# piezo-preamp-tickler_V0-5.net
KiCad netlist of a schematic drawn in EAGLE
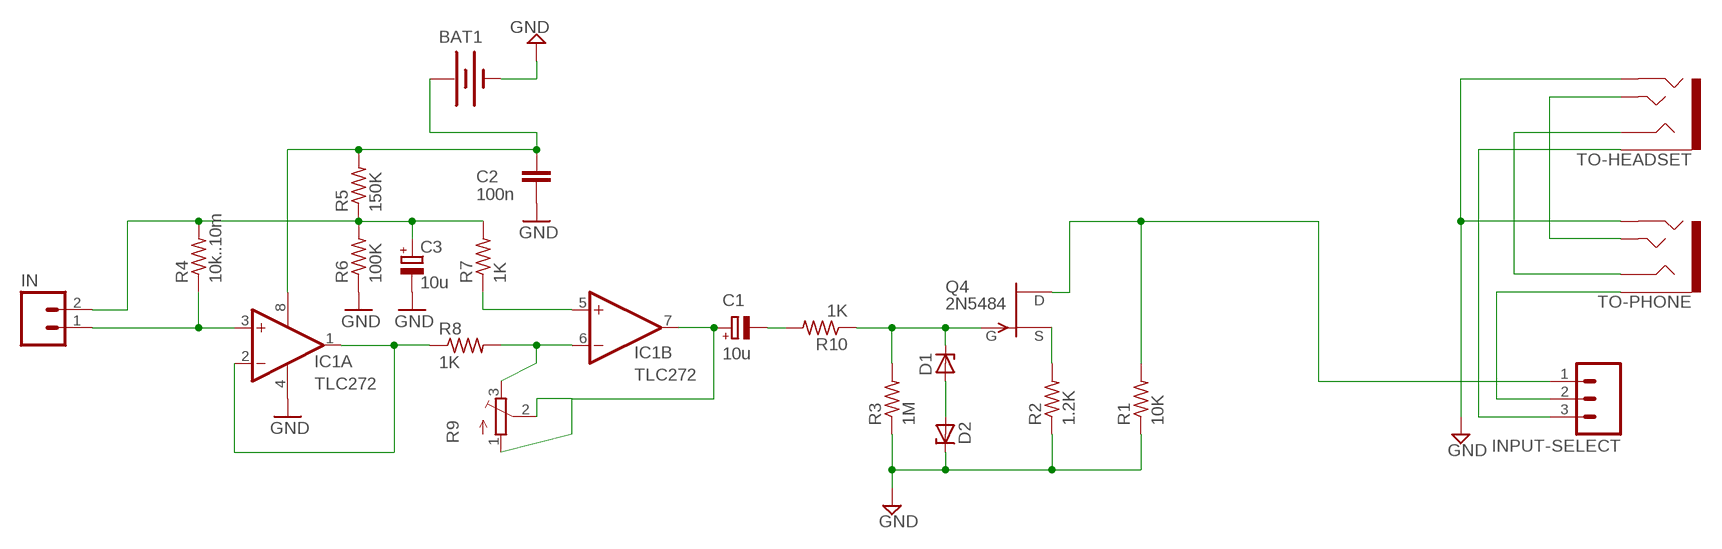
[diagram p0: schematic, sheet 1]

(export (version "E")
  (design (tool "Eeschema 10.0.6"))
  (components
    (comp (ref "BAT1")
      (value "BATTERYA23")
      (footprint "eagle-import:BATTERY-A23")
      (libsource (lib "eagle-import") (part "BATTERYA23"))
    )
    (comp (ref "C1")
      (value "10u")
      (footprint "eagle-import:E2,5-5")
      (libsource (lib "eagle-import") (part "CPOL-EUE2.5-5"))
    )
    (comp (ref "C2")
      (value "100n")
      (footprint "eagle-import:C025-025X050")
      (libsource (lib "eagle-import") (part "C-EU025-025X050"))
    )
    (comp (ref "C3")
      (value "10u")
      (footprint "eagle-import:E2,5-5")
      (libsource (lib "eagle-import") (part "CPOL-EUE2.5-5"))
    )
    (comp (ref "D1")
      (value "1N821")
      (footprint "eagle-import:DO35Z10")
      (libsource (lib "eagle-import") (part "1N821"))
    )
    (comp (ref "D2")
      (value "1N821")
      (footprint "eagle-import:DO35Z10")
      (libsource (lib "eagle-import") (part "1N821"))
    )
    (comp (ref "IC1")
      (value "TLC272")
      (footprint "eagle-import:DIL08")
      (libsource (lib "eagle-import") (part "TLC272P"))
    )
    (comp (ref "IN")
      (value "M02LOCK")
      (footprint "eagle-import:1X02_LOCK")
      (libsource (lib "eagle-import") (part "M02LOCK"))
    )
    (comp (ref "INPUT-SELECT")
      (value "M03LOCK")
      (footprint "eagle-import:1X03_LOCK")
      (libsource (lib "eagle-import") (part "M03LOCK"))
    )
    (comp (ref "Q4")
      (value "2N5484")
      (footprint "eagle-import:TO92-")
      (libsource (lib "eagle-import") (part "?5482N4"))
    )
    (comp (ref "R1")
      (value "10K")
      (footprint "eagle-import:0204V")
      (libsource (lib "eagle-import") (part "R-US_0204/2V"))
    )
    (comp (ref "R2")
      (value "1.2K")
      (footprint "eagle-import:0204V")
      (libsource (lib "eagle-import") (part "R-US_0204/2V"))
    )
    (comp (ref "R3")
      (value "1M")
      (footprint "eagle-import:0204V")
      (libsource (lib "eagle-import") (part "R-US_0204/2V"))
    )
    (comp (ref "R4")
      (value "10k..10m")
      (footprint "eagle-import:0204V")
      (libsource (lib "eagle-import") (part "R-US_0204/2V"))
    )
    (comp (ref "R5")
      (value "150K")
      (footprint "eagle-import:0204V")
      (libsource (lib "eagle-import") (part "R-US_0204/2V"))
    )
    (comp (ref "R6")
      (value "100K")
      (footprint "eagle-import:0204V")
      (libsource (lib "eagle-import") (part "R-US_0204/2V"))
    )
    (comp (ref "R7")
      (value "1K")
      (footprint "eagle-import:0204V")
      (libsource (lib "eagle-import") (part "R-US_0204/2V"))
    )
    (comp (ref "R8")
      (value "1K")
      (footprint "eagle-import:0204V")
      (libsource (lib "eagle-import") (part "R-US_0204/2V"))
    )
    (comp (ref "R9")
      (value "TRIMPOT3386")
      (footprint "eagle-import:TRIM-3386")
      (libsource (lib "eagle-import") (part "TRIMPOT3386"))
    )
    (comp (ref "R10")
      (value "1K")
      (footprint "eagle-import:0204V")
      (libsource (lib "eagle-import") (part "R-US_0204/2V"))
    )
    (comp (ref "TO-HEADSET")
      (value "AUDIO-JACK3")
      (footprint "eagle-import:AUDIO-JACK-TRRS-SMD")
      (libsource (lib "eagle-import") (part "AUDIO-JACK3"))
    )
    (comp (ref "TO-PHONE")
      (value "AUDIO-JACK3")
      (footprint "eagle-import:AUDIO-JACK-TRRS-SMD")
      (libsource (lib "eagle-import") (part "AUDIO-JACK3"))
    )
  )
  (nets
    (net (code "1") (name "GND") (class "Default")
      (node (ref "BAT1") (pin "GND@1") (pinfunction "-_GND@1") (pintype "power_in"))
      (node (ref "C2") (pin "1") (pinfunction "1_1") (pintype "passive"))
      (node (ref "C3") (pin "-") (pinfunction "-_-") (pintype "passive"))
      (node (ref "D2") (pin "C") (pinfunction "C_C") (pintype "passive"))
      (node (ref "IC1") (pin "4") (pinfunction "V-_4") (pintype "power_in"))
      (node (ref "R1") (pin "1") (pinfunction "1_1") (pintype "passive"))
      (node (ref "R2") (pin "1") (pinfunction "1_1") (pintype "passive"))
      (node (ref "R3") (pin "1") (pinfunction "1_1") (pintype "passive"))
      (node (ref "R6") (pin "1") (pinfunction "1_1") (pintype "passive"))
      (node (ref "TO-HEADSET") (pin "RING2") (pinfunction "RING2_RING2") (pintype "bidirectional"))
      (node (ref "TO-PHONE") (pin "RING2") (pinfunction "RING2_RING2") (pintype "bidirectional"))
    )
    (net (code "2") (name "Net-(BAT1-+)") (class "Default")
      (node (ref "BAT1") (pin "PWR@1") (pinfunction "+_PWR@1") (pintype "power_in"))
      (node (ref "C2") (pin "2") (pinfunction "2_2") (pintype "passive"))
      (node (ref "IC1") (pin "8") (pinfunction "V+_8") (pintype "power_in"))
      (node (ref "R5") (pin "2") (pinfunction "2_2") (pintype "passive"))
    )
    (net (code "3") (name "Net-(C1-Pad-)") (class "Default")
      (node (ref "C1") (pin "-") (pinfunction "-_-") (pintype "passive"))
      (node (ref "R10") (pin "2") (pinfunction "2_2") (pintype "passive"))
    )
    (net (code "4") (name "Net-(C3-Pad+)") (class "Default")
      (node (ref "C3") (pin "+") (pinfunction "+_+") (pintype "passive"))
      (node (ref "IN") (pin "2") (pinfunction "2_2") (pintype "passive"))
      (node (ref "R4") (pin "2") (pinfunction "2_2") (pintype "passive"))
      (node (ref "R5") (pin "1") (pinfunction "1_1") (pintype "passive"))
      (node (ref "R6") (pin "2") (pinfunction "2_2") (pintype "passive"))
      (node (ref "R7") (pin "2") (pinfunction "2_2") (pintype "passive"))
    )
    (net (code "5") (name "Net-(D1-PadA)") (class "Default")
      (node (ref "D1") (pin "A") (pinfunction "A_A") (pintype "passive"))
      (node (ref "D2") (pin "A") (pinfunction "A_A") (pintype "passive"))
    )
    (net (code "6") (name "Net-(IC1A-+IN)") (class "Default")
      (node (ref "IC1") (pin "3") (pinfunction "+IN_3") (pintype "input"))
      (node (ref "IN") (pin "1") (pinfunction "1_1") (pintype "passive"))
      (node (ref "R4") (pin "1") (pinfunction "1_1") (pintype "passive"))
    )
    (net (code "7") (name "Net-(IC1A--IN)") (class "Default")
      (node (ref "IC1") (pin "1") (pinfunction "OUT_1") (pintype "output"))
      (node (ref "IC1") (pin "2") (pinfunction "-IN_2") (pintype "input"))
      (node (ref "R8") (pin "1") (pinfunction "1_1") (pintype "passive"))
    )
    (net (code "8") (name "Net-(IC1B-+IN)") (class "Default")
      (node (ref "IC1") (pin "5") (pinfunction "+IN_5") (pintype "input"))
      (node (ref "R7") (pin "1") (pinfunction "1_1") (pintype "passive"))
    )
    (net (code "9") (name "Net-(IC1B--IN)") (class "Default")
      (node (ref "IC1") (pin "6") (pinfunction "-IN_6") (pintype "input"))
      (node (ref "R8") (pin "2") (pinfunction "2_2") (pintype "passive"))
      (node (ref "R9") (pin "3") (pinfunction "E_3") (pintype "passive"))
    )
    (net (code "10") (name "Net-(IC1B-OUT)") (class "Default")
      (node (ref "C1") (pin "+") (pinfunction "+_+") (pintype "passive"))
      (node (ref "IC1") (pin "7") (pinfunction "OUT_7") (pintype "output"))
      (node (ref "R9") (pin "1") (pinfunction "A_1") (pintype "passive"))
      (node (ref "R9") (pin "2") (pinfunction "S_2") (pintype "passive"))
    )
    (net (code "11") (name "Net-(INPUT-SELECT-Pad2)") (class "Default")
      (node (ref "INPUT-SELECT") (pin "2") (pinfunction "2_2") (pintype "passive"))
      (node (ref "TO-PHONE") (pin "EARTH") (pinfunction "EARTH_EARTH") (pintype "bidirectional"))
    )
    (net (code "12") (name "Net-(INPUT-SELECT-Pad3)") (class "Default")
      (node (ref "INPUT-SELECT") (pin "3") (pinfunction "3_3") (pintype "passive"))
      (node (ref "TO-HEADSET") (pin "EARTH") (pinfunction "EARTH_EARTH") (pintype "bidirectional"))
    )
    (net (code "13") (name "Net-(Q4-D)") (class "Default")
      (node (ref "INPUT-SELECT") (pin "1") (pinfunction "1_1") (pintype "passive"))
      (node (ref "Q4") (pin "3") (pinfunction "D_3") (pintype "passive"))
      (node (ref "R1") (pin "2") (pinfunction "2_2") (pintype "passive"))
    )
    (net (code "14") (name "Net-(Q4-G)") (class "Default")
      (node (ref "D1") (pin "C") (pinfunction "C_C") (pintype "passive"))
      (node (ref "Q4") (pin "1") (pinfunction "G_1") (pintype "passive"))
      (node (ref "R10") (pin "1") (pinfunction "1_1") (pintype "passive"))
      (node (ref "R3") (pin "2") (pinfunction "2_2") (pintype "passive"))
    )
    (net (code "15") (name "Net-(Q4-S)") (class "Default")
      (node (ref "Q4") (pin "2") (pinfunction "S_2") (pintype "passive"))
      (node (ref "R2") (pin "2") (pinfunction "2_2") (pintype "passive"))
    )
    (net (code "16") (name "Net-(TO-HEADSET-PadRING1)") (class "Default")
      (node (ref "TO-HEADSET") (pin "RING1") (pinfunction "RING1_RING1") (pintype "bidirectional"))
      (node (ref "TO-PHONE") (pin "RING1") (pinfunction "RING1_RING1") (pintype "bidirectional"))
    )
    (net (code "17") (name "Net-(TO-HEADSET-PadTIP)") (class "Default")
      (node (ref "TO-HEADSET") (pin "TIP") (pinfunction "TIP_TIP") (pintype "bidirectional"))
      (node (ref "TO-PHONE") (pin "TIP") (pinfunction "TIP_TIP") (pintype "bidirectional"))
    )
  )
)
